# External_IO_Protection.net
KiCad netlist of a schematic drawn in Altium Designer
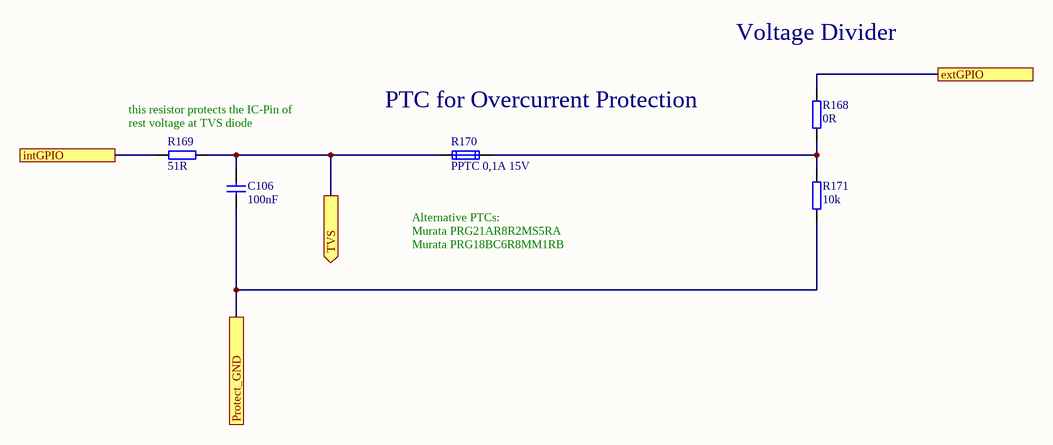
[diagram p0: External_IO_Protection.SchDoc]

(export (version "E")
  (design (tool "Eeschema 10.0.6"))
  (components
    (comp (ref "C106")
      (value "100nF")
      (footprint "CAPC1608X90N_V")
      (description "KON 100nF 50V X7R ±10% SMD BF 1608 (0603)")
      (fields (field (name "TOLERANCE") "±10%") (field (name "VOLTAGE") "50V"))
      (libsource (lib "TE") (part "CAP-NP"))
    )
    (comp (ref "R168")
      (value "0R")
      (footprint "R_0603_TE")
      (description "Generic resistor")
      (fields
        (field (name "TOLERANCE") "1 %")
        (field (name "MANUFACTURER PART NUMBER") "UZgen_R_0603_0R")
        (field (name "CREATED FROM") "UZgenTool")
      )
      (libsource (lib "user") (part "RES"))
    )
    (comp (ref "R169")
      (value "51R")
      (footprint "RESC1608X55N_V")
      (description "WID SMD 51R 1% 0,1W  BF 1608 (0603)")
      (fields (field (name "TOLERANCE") "1%"))
      (libsource (lib "TE") (part "RES"))
    )
    (comp (ref "R170")
      (value "PPTC 0,1A 15V")
      (footprint "RESC2012X85N")
      (description "PTC Resettable Fuse 0.1A 15V SMD 0805")
      (fields (field (name "VOLTAGE") "15V"))
      (libsource (lib "TE") (part "Polyswitch"))
    )
    (comp (ref "R171")
      (value "10k")
      (footprint "R_0603_TE")
      (description "Generic resistor")
      (fields
        (field (name "TOLERANCE") "1 %")
        (field (name "MANUFACTURER PART NUMBER") "UZgen_R_0603_10k")
        (field (name "CREATED FROM") "AGeiger")
      )
      (libsource (lib "user") (part "RES"))
    )
  )
  (nets
    (net (code "1") (name "/Protect_GND") (class "Default")
      (node (ref "C106") (pin "1") (pinfunction "1_1") (pintype "passive"))
      (node (ref "R171") (pin "2") (pinfunction "2_2") (pintype "passive"))
    )
    (net (code "2") (name "/TVS") (class "Default")
      (node (ref "C106") (pin "2") (pinfunction "2_2") (pintype "passive"))
      (node (ref "R169") (pin "1") (pinfunction "1_1") (pintype "passive"))
      (node (ref "R170") (pin "1") (pinfunction "1_1") (pintype "passive"))
    )
    (net (code "3") (name "/extGPIO") (class "Default")
      (node (ref "R168") (pin "2") (pinfunction "2_2") (pintype "passive"))
    )
    (net (code "4") (name "/intGPIO") (class "Default")
      (node (ref "R169") (pin "2") (pinfunction "2_2") (pintype "passive"))
    )
    (net (code "5") (name "Net-(R168-Pad1)") (class "Default")
      (node (ref "R168") (pin "1") (pinfunction "1_1") (pintype "passive"))
      (node (ref "R170") (pin "2") (pinfunction "2_2") (pintype "passive"))
      (node (ref "R171") (pin "1") (pinfunction "1_1") (pintype "passive"))
    )
  )
)
